# Linear_patch.net
KiCad netlist of a schematic drawn in Altium Designer
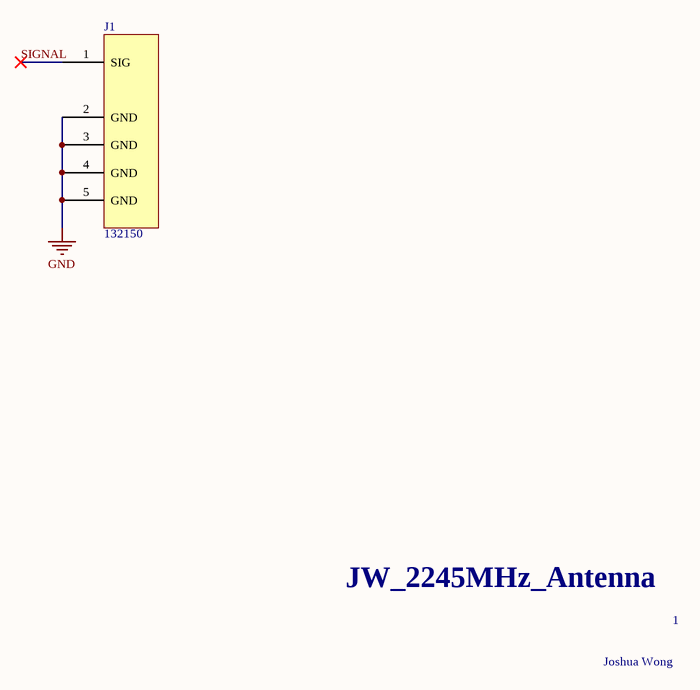
[diagram p0: Linear_patch.SchDoc]

(export (version "E")
  (design (tool "Eeschema 10.0.6"))
  (components
    (comp (ref "J1")
      (value "132150")
      (footprint "132150-Footprint-1")
      (description "CONN SMA RCPT STR 50 OHM SOLDER")
      (libsource (lib "University of Toronto Aerospace Team") (part "132150-Symbol-1"))
    )
  )
  (nets
    (net (code "1") (name "/SIGNAL") (class "Default")
      (node (ref "J1") (pin "1") (pinfunction "SIG_1") (pintype "passive+no_connect"))
    )
    (net (code "2") (name "GND") (class "Default")
      (node (ref "J1") (pin "2") (pinfunction "GND_2") (pintype "passive"))
      (node (ref "J1") (pin "3") (pinfunction "GND_3") (pintype "passive"))
      (node (ref "J1") (pin "4") (pinfunction "GND_4") (pintype "passive"))
      (node (ref "J1") (pin "5") (pinfunction "GND_5") (pintype "passive"))
    )
  )
)
